# DAC_8Bit.net
KiCad netlist of a schematic drawn in Altium Designer
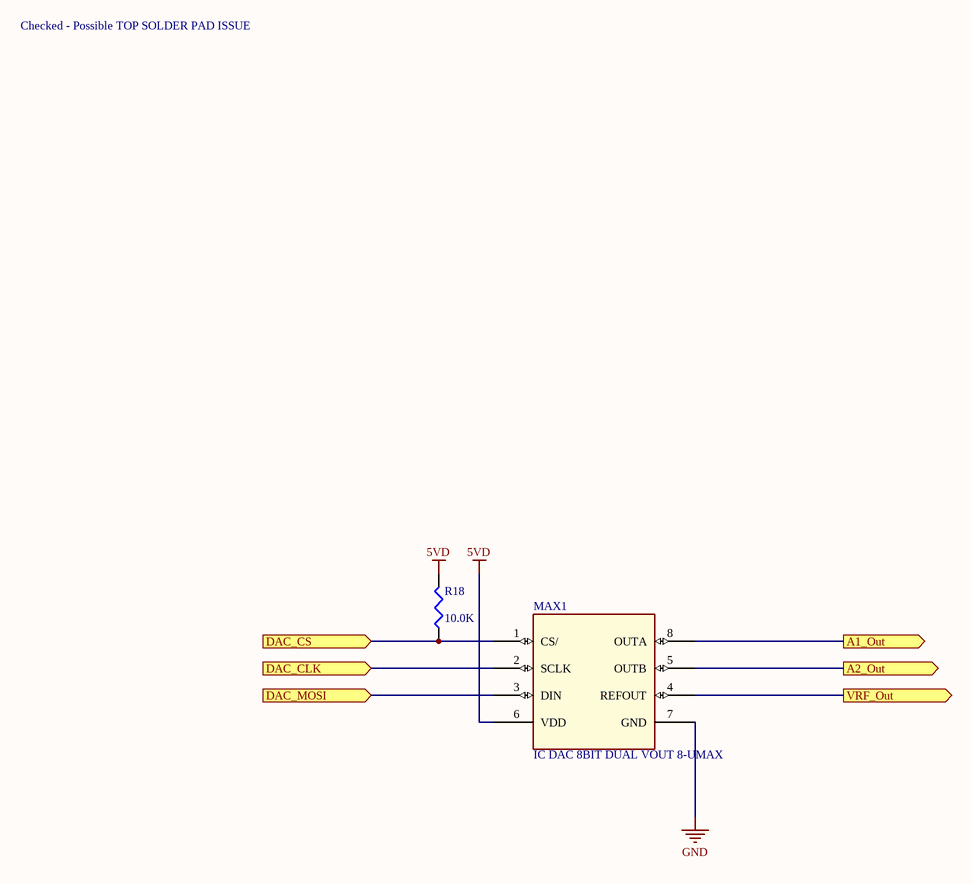
[diagram p0: DAC_8Bit.SchDoc]

(export (version "E")
  (design (tool "Eeschema 10.0.6"))
  (components
    (comp (ref "MAX1")
      (value "IC DAC 8BIT DUAL VOUT 8-UMAX")
      (footprint "TSOP65P490X110-8M")
      (fields (field (name "MPN") "MAX5513EUA+"))
      (libsource (lib "esd_library") (part "Max5513-dac"))
    )
    (comp (ref "R18")
      (value "10.0K")
      (footprint "RESC2112X05M")
      (description "RES SMD 10.0K OHM 1% 1/8W 0805")
      (fields (field (name "MPN") "CRCW080510K0FKEA") (field (name "Comment") "Res3"))
      (libsource (lib "esd_library") (part "Resistor_10.0K"))
    )
  )
  (nets
    (net (code "1") (name "/A1_Out") (class "Default")
      (node (ref "MAX1") (pin "8") (pinfunction "OUTA_8") (pintype "bidirectional"))
    )
    (net (code "2") (name "/A2_Out") (class "Default")
      (node (ref "MAX1") (pin "5") (pinfunction "OUTB_5") (pintype "bidirectional"))
    )
    (net (code "3") (name "/DAC_CLK") (class "Default")
      (node (ref "MAX1") (pin "2") (pinfunction "SCLK_2") (pintype "bidirectional"))
    )
    (net (code "4") (name "/DAC_CS") (class "Default")
      (node (ref "MAX1") (pin "1") (pinfunction "CS/_1") (pintype "bidirectional"))
      (node (ref "R18") (pin "1") (pinfunction "1_1") (pintype "passive"))
    )
    (net (code "5") (name "/DAC_MOSI") (class "Default")
      (node (ref "MAX1") (pin "3") (pinfunction "DIN_3") (pintype "bidirectional"))
    )
    (net (code "6") (name "/VRF_Out") (class "Default")
      (node (ref "MAX1") (pin "4") (pinfunction "REFOUT_4") (pintype "bidirectional"))
    )
    (net (code "7") (name "5VD") (class "Default")
      (node (ref "MAX1") (pin "6") (pinfunction "VDD_6") (pintype "power_in"))
      (node (ref "R18") (pin "2") (pinfunction "2_2") (pintype "passive"))
    )
    (net (code "8") (name "GND") (class "Default")
      (node (ref "MAX1") (pin "7") (pinfunction "GND_7") (pintype "power_in"))
    )
  )
)
